# SCH.net
KiCad netlist of a schematic drawn in Altium Designer
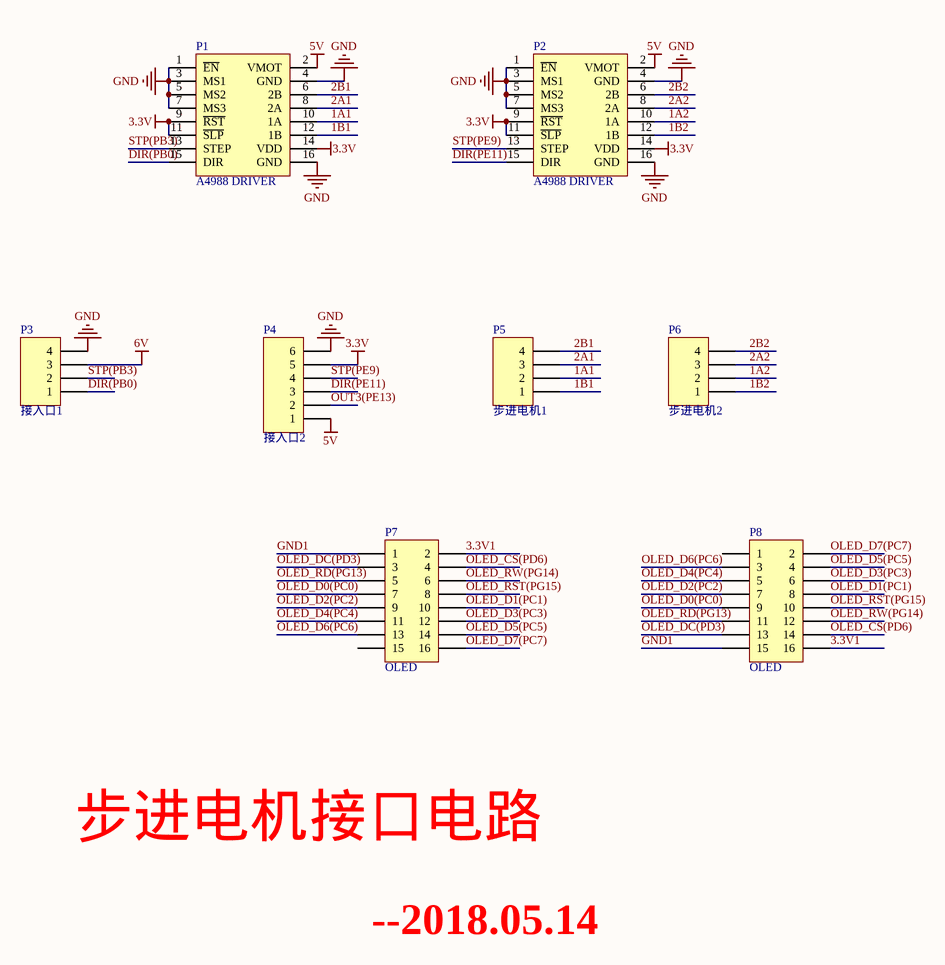
[diagram p0: 电机驱动SCH.SchDoc]

(export (version "E")
  (design (tool "Eeschema 10.0.6"))
  (components
    (comp (ref "P1")
      (value "A4988 DRIVER")
      (footprint "A4988")
      (description "A4988步进电机驱动模块")
      (libsource (lib "Miscellaneous Connectors") (part "A4988 DRIVER"))
    )
    (comp (ref "P2")
      (value "A4988 DRIVER")
      (footprint "A4988")
      (description "A4988步进电机驱动模块")
      (libsource (lib "Miscellaneous Connectors") (part "A4988 DRIVER"))
    )
    (comp (ref "P3")
      (value "接入口1")
      (footprint "HDR1X4")
      (description "Header, 4-Pin")
      (fields (field (name "PUBLISHER") "Altium Limited"))
      (libsource (lib "九轴数据采集") (part "Header 4"))
    )
    (comp (ref "P4")
      (value "接入口2")
      (footprint "HDR1X6")
      (description "Header, 6-Pin")
      (fields (field (name "PUBLISHER") "Altium Limited"))
      (libsource (lib "Miscellaneous Connectors") (part "Header 6"))
    )
    (comp (ref "P5")
      (value "步进电机1")
      (footprint "HDR1X4")
      (description "Header, 4-Pin")
      (fields (field (name "PUBLISHER") "Altium Limited"))
      (libsource (lib "Miscellaneous Connectors") (part "Header 4"))
    )
    (comp (ref "P6")
      (value "步进电机2")
      (footprint "HDR1X4")
      (description "Header, 4-Pin")
      (fields (field (name "PUBLISHER") "Altium Limited"))
      (libsource (lib "Miscellaneous Connectors") (part "Header 4"))
    )
    (comp (ref "P7")
      (value "OLED")
      (footprint "HDR2X8")
      (description "Header, 8-Pin, Dual row")
      (fields (field (name "PUBLISHER") "Altium Limited"))
      (libsource (lib "Miscellaneous Connectors") (part "Header 8X2"))
    )
    (comp (ref "P8")
      (value "OLED")
      (footprint "HDR2X8")
      (description "Header, 8-Pin, Dual row")
      (fields (field (name "PUBLISHER") "Altium Limited"))
      (libsource (lib "Miscellaneous Connectors") (part "Header 8X2"))
    )
  )
  (nets
    (net (code "1") (name "/1A1") (class "Default")
      (node (ref "P1") (pin "10") (pinfunction "1A_10") (pintype "passive"))
      (node (ref "P5") (pin "2") (pinfunction "2_2") (pintype "passive"))
    )
    (net (code "2") (name "/1A2") (class "Default")
      (node (ref "P2") (pin "10") (pinfunction "1A_10") (pintype "passive"))
      (node (ref "P6") (pin "2") (pinfunction "2_2") (pintype "passive"))
    )
    (net (code "3") (name "/1B1") (class "Default")
      (node (ref "P1") (pin "12") (pinfunction "1B_12") (pintype "passive"))
      (node (ref "P5") (pin "1") (pinfunction "1_1") (pintype "passive"))
    )
    (net (code "4") (name "/1B2") (class "Default")
      (node (ref "P2") (pin "12") (pinfunction "1B_12") (pintype "passive"))
      (node (ref "P6") (pin "1") (pinfunction "1_1") (pintype "passive"))
    )
    (net (code "5") (name "/2A1") (class "Default")
      (node (ref "P1") (pin "8") (pinfunction "2A_8") (pintype "passive"))
      (node (ref "P5") (pin "3") (pinfunction "3_3") (pintype "passive"))
    )
    (net (code "6") (name "/2A2") (class "Default")
      (node (ref "P2") (pin "8") (pinfunction "2A_8") (pintype "passive"))
      (node (ref "P6") (pin "3") (pinfunction "3_3") (pintype "passive"))
    )
    (net (code "7") (name "/2B1") (class "Default")
      (node (ref "P1") (pin "6") (pinfunction "2B_6") (pintype "passive"))
      (node (ref "P5") (pin "4") (pinfunction "4_4") (pintype "passive"))
    )
    (net (code "8") (name "/2B2") (class "Default")
      (node (ref "P2") (pin "6") (pinfunction "2B_6") (pintype "passive"))
      (node (ref "P6") (pin "4") (pinfunction "4_4") (pintype "passive"))
    )
    (net (code "9") (name "/3.3V1") (class "Default")
      (node (ref "P7") (pin "2") (pinfunction "2_2") (pintype "passive"))
      (node (ref "P8") (pin "16") (pinfunction "16_16") (pintype "passive"))
    )
    (net (code "10") (name "/DIR(PB0)") (class "Default")
      (node (ref "P1") (pin "15") (pinfunction "DIR_15") (pintype "passive"))
      (node (ref "P3") (pin "1") (pinfunction "1_1") (pintype "passive"))
    )
    (net (code "11") (name "/DIR(PE11)") (class "Default")
      (node (ref "P2") (pin "15") (pinfunction "DIR_15") (pintype "passive"))
      (node (ref "P4") (pin "3") (pinfunction "3_3") (pintype "passive"))
    )
    (net (code "12") (name "/GND1") (class "Default")
      (node (ref "P7") (pin "1") (pinfunction "1_1") (pintype "passive"))
      (node (ref "P8") (pin "15") (pinfunction "15_15") (pintype "passive"))
    )
    (net (code "13") (name "/OLED_CS(PD6)") (class "Default")
      (node (ref "P7") (pin "4") (pinfunction "4_4") (pintype "passive"))
      (node (ref "P8") (pin "14") (pinfunction "14_14") (pintype "passive"))
    )
    (net (code "14") (name "/OLED_D0(PC0)") (class "Default")
      (node (ref "P7") (pin "7") (pinfunction "7_7") (pintype "passive"))
      (node (ref "P8") (pin "9") (pinfunction "9_9") (pintype "passive"))
    )
    (net (code "15") (name "/OLED_D1(PC1)") (class "Default")
      (node (ref "P7") (pin "10") (pinfunction "10_10") (pintype "passive"))
      (node (ref "P8") (pin "8") (pinfunction "8_8") (pintype "passive"))
    )
    (net (code "16") (name "/OLED_D2(PC2)") (class "Default")
      (node (ref "P7") (pin "9") (pinfunction "9_9") (pintype "passive"))
      (node (ref "P8") (pin "7") (pinfunction "7_7") (pintype "passive"))
    )
    (net (code "17") (name "/OLED_D3(PC3)") (class "Default")
      (node (ref "P7") (pin "12") (pinfunction "12_12") (pintype "passive"))
      (node (ref "P8") (pin "6") (pinfunction "6_6") (pintype "passive"))
    )
    (net (code "18") (name "/OLED_D4(PC4)") (class "Default")
      (node (ref "P7") (pin "11") (pinfunction "11_11") (pintype "passive"))
      (node (ref "P8") (pin "5") (pinfunction "5_5") (pintype "passive"))
    )
    (net (code "19") (name "/OLED_D5(PC5)") (class "Default")
      (node (ref "P7") (pin "14") (pinfunction "14_14") (pintype "passive"))
      (node (ref "P8") (pin "4") (pinfunction "4_4") (pintype "passive"))
    )
    (net (code "20") (name "/OLED_D6(PC6)") (class "Default")
      (node (ref "P7") (pin "13") (pinfunction "13_13") (pintype "passive"))
      (node (ref "P8") (pin "3") (pinfunction "3_3") (pintype "passive"))
    )
    (net (code "21") (name "/OLED_D7(PC7)") (class "Default")
      (node (ref "P7") (pin "16") (pinfunction "16_16") (pintype "passive"))
      (node (ref "P8") (pin "2") (pinfunction "2_2") (pintype "passive"))
    )
    (net (code "22") (name "/OLED_DC(PD3)") (class "Default")
      (node (ref "P7") (pin "3") (pinfunction "3_3") (pintype "passive"))
      (node (ref "P8") (pin "13") (pinfunction "13_13") (pintype "passive"))
    )
    (net (code "23") (name "/OLED_RD(PG13)") (class "Default")
      (node (ref "P7") (pin "5") (pinfunction "5_5") (pintype "passive"))
      (node (ref "P8") (pin "11") (pinfunction "11_11") (pintype "passive"))
    )
    (net (code "24") (name "/OLED_RST(PG15)") (class "Default")
      (node (ref "P7") (pin "8") (pinfunction "8_8") (pintype "passive"))
      (node (ref "P8") (pin "10") (pinfunction "10_10") (pintype "passive"))
    )
    (net (code "25") (name "/OLED_RW(PG14)") (class "Default")
      (node (ref "P7") (pin "6") (pinfunction "6_6") (pintype "passive"))
      (node (ref "P8") (pin "12") (pinfunction "12_12") (pintype "passive"))
    )
    (net (code "26") (name "/OUT3(PE13)") (class "Default")
      (node (ref "P4") (pin "2") (pinfunction "2_2") (pintype "passive"))
    )
    (net (code "27") (name "/STP(PB3)") (class "Default")
      (node (ref "P1") (pin "13") (pinfunction "STEP_13") (pintype "passive"))
      (node (ref "P3") (pin "2") (pinfunction "2_2") (pintype "passive"))
    )
    (net (code "28") (name "/STP(PE9)") (class "Default")
      (node (ref "P2") (pin "13") (pinfunction "STEP_13") (pintype "passive"))
      (node (ref "P4") (pin "4") (pinfunction "4_4") (pintype "passive"))
    )
    (net (code "29") (name "3.3V") (class "Default")
      (node (ref "P1") (pin "11") (pinfunction "~{SLP}_11") (pintype "passive"))
      (node (ref "P1") (pin "14") (pinfunction "VDD_14") (pintype "passive"))
      (node (ref "P1") (pin "9") (pinfunction "~{RST}_9") (pintype "passive"))
      (node (ref "P2") (pin "11") (pinfunction "~{SLP}_11") (pintype "passive"))
      (node (ref "P2") (pin "14") (pinfunction "VDD_14") (pintype "passive"))
      (node (ref "P2") (pin "9") (pinfunction "~{RST}_9") (pintype "passive"))
      (node (ref "P4") (pin "5") (pinfunction "5_5") (pintype "passive"))
    )
    (net (code "30") (name "5V") (class "Default")
      (node (ref "P1") (pin "2") (pinfunction "VMOT_2") (pintype "passive"))
      (node (ref "P2") (pin "2") (pinfunction "VMOT_2") (pintype "passive"))
      (node (ref "P4") (pin "1") (pinfunction "1_1") (pintype "passive"))
    )
    (net (code "31") (name "6V") (class "Default")
      (node (ref "P3") (pin "3") (pinfunction "3_3") (pintype "passive"))
    )
    (net (code "32") (name "GND") (class "Default")
      (node (ref "P1") (pin "1") (pinfunction "~{EN}_1") (pintype "passive"))
      (node (ref "P1") (pin "16") (pinfunction "GND_16") (pintype "passive"))
      (node (ref "P1") (pin "3") (pinfunction "MS1_3") (pintype "passive"))
      (node (ref "P1") (pin "4") (pinfunction "GND_4") (pintype "passive"))
      (node (ref "P1") (pin "5") (pinfunction "MS2_5") (pintype "passive"))
      (node (ref "P1") (pin "7") (pinfunction "MS3_7") (pintype "passive"))
      (node (ref "P2") (pin "1") (pinfunction "~{EN}_1") (pintype "passive"))
      (node (ref "P2") (pin "16") (pinfunction "GND_16") (pintype "passive"))
      (node (ref "P2") (pin "3") (pinfunction "MS1_3") (pintype "passive"))
      (node (ref "P2") (pin "4") (pinfunction "GND_4") (pintype "passive"))
      (node (ref "P2") (pin "5") (pinfunction "MS2_5") (pintype "passive"))
      (node (ref "P2") (pin "7") (pinfunction "MS3_7") (pintype "passive"))
      (node (ref "P3") (pin "4") (pinfunction "4_4") (pintype "passive"))
      (node (ref "P4") (pin "6") (pinfunction "6_6") (pintype "passive"))
    )
    (net (code "33") (name "unconnected-(P7-Pad15)") (class "Default")
      (node (ref "P7") (pin "15") (pinfunction "15_15") (pintype "passive"))
    )
    (net (code "34") (name "unconnected-(P8-Pad1)") (class "Default")
      (node (ref "P8") (pin "1") (pinfunction "1_1") (pintype "passive"))
    )
  )
)
